# GadgetBox-Propeller.net
KiCad netlist of a schematic drawn in EAGLE
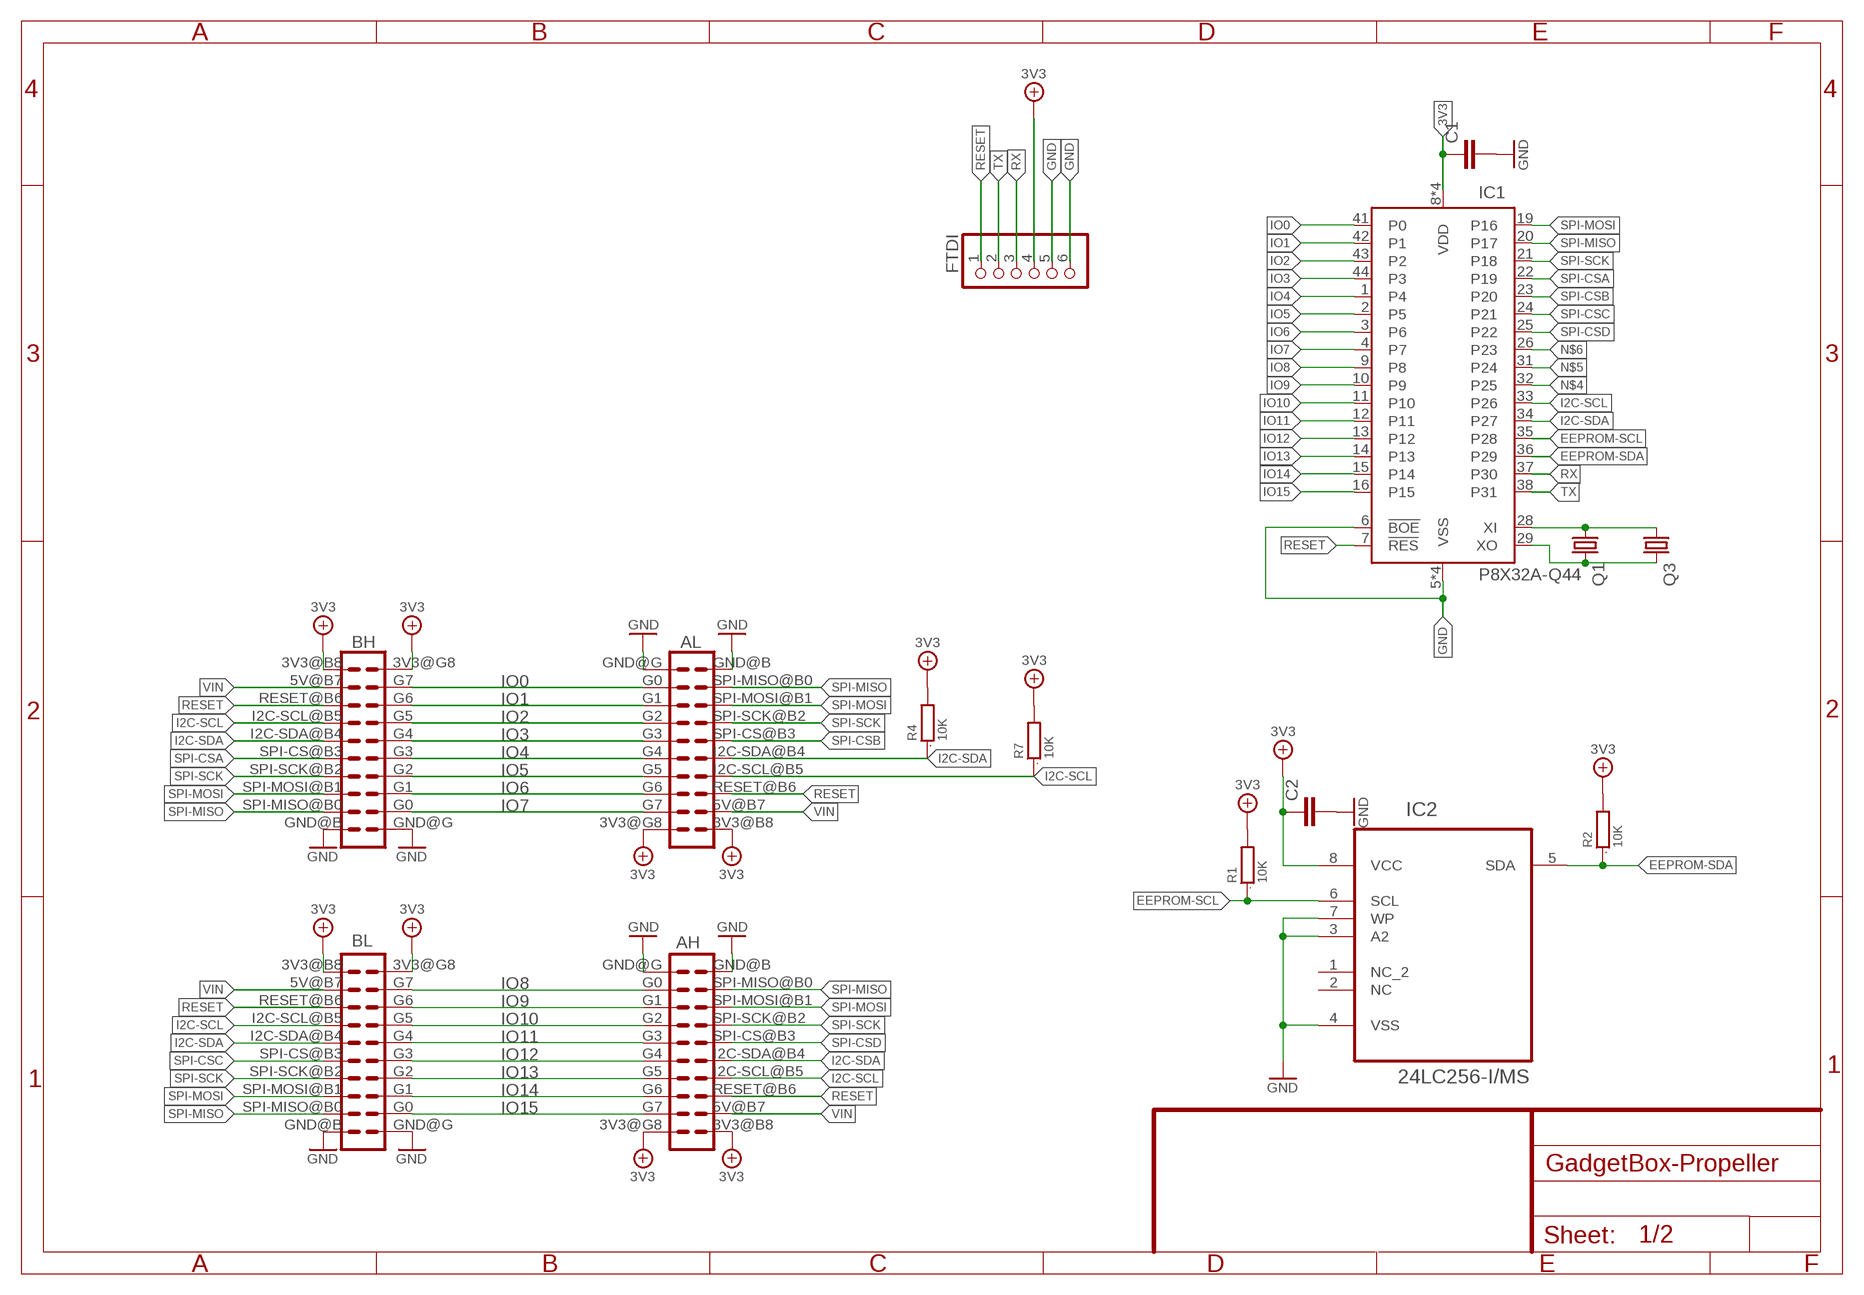
[diagram p0: schematic, sheet 1]
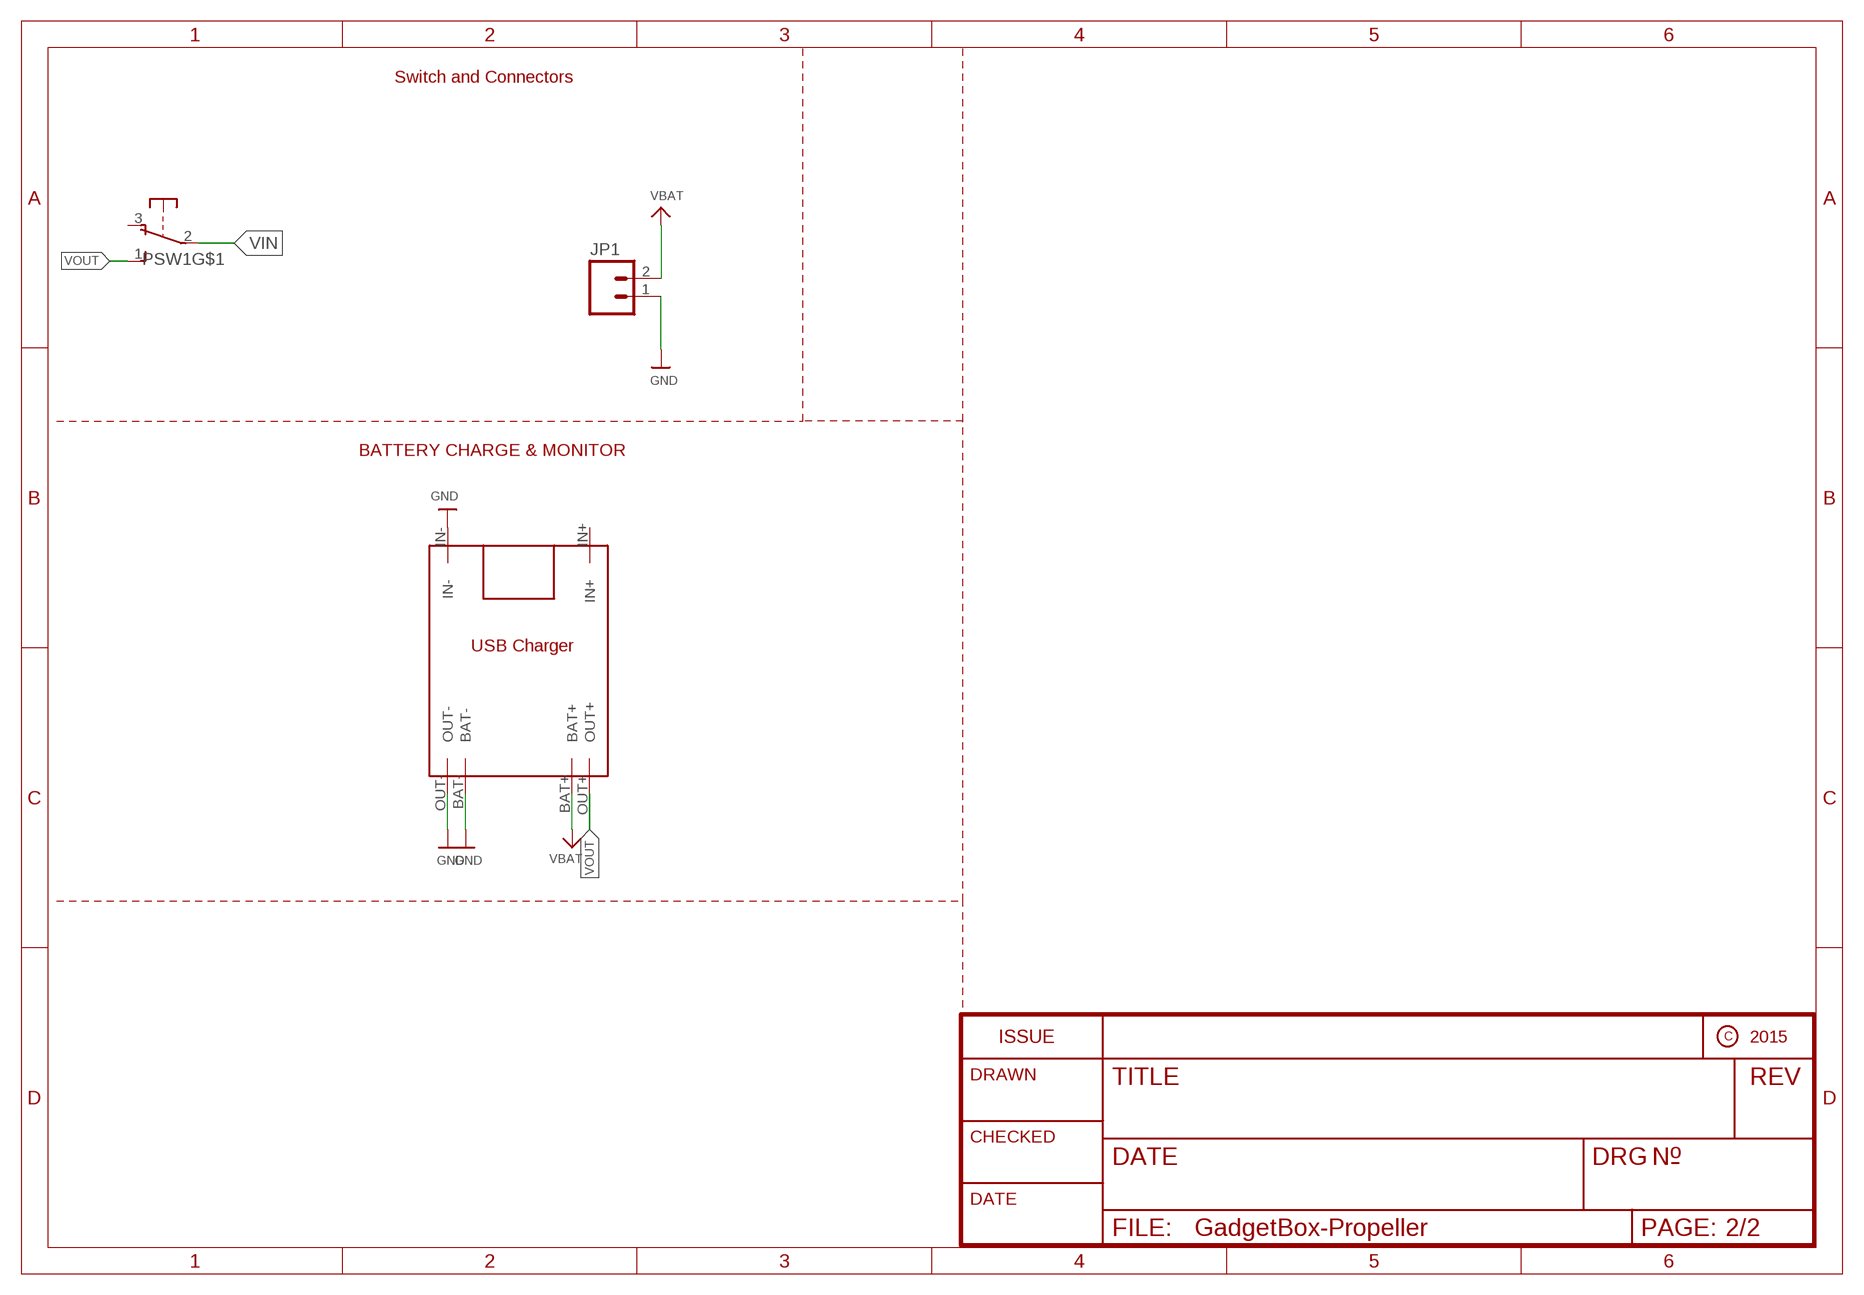
[diagram p1: schematic, sheet 2]

(export (version "E")
  (design (tool "Eeschema 10.0.6"))
  (components
    (comp (ref "JP1")
      (value "M02-JST-2-PTH-NO_SILK")
      (footprint "eagle-import:JST-2-PTH-NS")
      (libsource (lib "eagle-import") (part "M02-JST-2-PTH-NO_SILK"))
    )
    (comp (ref "PSW1")
      (value "OS102011MA1Q")
      (footprint "eagle-import:OS102011MA1Q")
      (fields
        (field (name "PARTNO") "OS102011MA1QN1,C&K Components,dk,CKN9559-ND,SWITCH SLIDE SPDT 100MA 12V , REF72")
      )
      (libsource (lib "eagle-import") (part "OS102011MA1Q"))
    )
    (comp (ref "U$5")
      (value "TP4056")
      (footprint "eagle-import:TP4056")
      (libsource (lib "eagle-import") (part "TP4056"))
    )
    (comp (ref "AH")
      (value "ECOGECOG_SLOT_ALT1")
      (footprint "eagle-import:ECOG_ALT1")
      (libsource (lib "eagle-import") (part "ECOGECOG_SLOT_ALT1"))
    )
    (comp (ref "AL")
      (value "ECOGECOG_SLOT_ALT1")
      (footprint "eagle-import:ECOG_ALT1")
      (libsource (lib "eagle-import") (part "ECOGECOG_SLOT_ALT1"))
    )
    (comp (ref "BH")
      (value "ECOGECOG_SLOT_ALT1")
      (footprint "eagle-import:ECOG_ALT1")
      (libsource (lib "eagle-import") (part "ECOGECOG_SLOT_ALT1"))
    )
    (comp (ref "BL")
      (value "ECOGECOG_SLOT_ALT1")
      (footprint "eagle-import:ECOG_ALT1")
      (libsource (lib "eagle-import") (part "ECOGECOG_SLOT_ALT1"))
    )
    (comp (ref "C1")
      (value "CAP0805")
      (footprint "eagle-import:0805")
      (libsource (lib "eagle-import") (part "CAP0805"))
    )
    (comp (ref "C2")
      (value "CAP0805")
      (footprint "eagle-import:0805")
      (libsource (lib "eagle-import") (part "CAP0805"))
    )
    (comp (ref "FTDI")
      (value "PINHD-1X6")
      (footprint "eagle-import:1X06")
      (libsource (lib "eagle-import") (part "PINHD-1X6"))
    )
    (comp (ref "IC1")
      (value "P8X32A-Q44")
      (footprint "eagle-import:LQFP44-10X10")
      (fields (field (name "MF") "Parallax Semiconductor"))
      (libsource (lib "eagle-import") (part "P8X32A-?Q44"))
    )
    (comp (ref "IC2")
      (value "24LC256-I/MS")
      (footprint "eagle-import:SOP65P490X110-8N")
      (libsource (lib "eagle-import") (part "24LC256-I/MS"))
    )
    (comp (ref "Q1")
      (value "CRYSTALSM49")
      (footprint "eagle-import:SM49")
      (libsource (lib "eagle-import") (part "CRYSTALSM49"))
    )
    (comp (ref "Q3")
      (value "CRYSTALHC49U-V")
      (footprint "eagle-import:HC49U-V")
      (libsource (lib "eagle-import") (part "CRYSTALHC49U-V"))
    )
    (comp (ref "R1")
      (value "10K")
      (footprint "eagle-import:0603")
      (fields
        (field (name "PARTNO") "RC0603JR-0710KL,YAGEO (VA),dk,311-10KGRCT-ND,RES SMD 10K OHM 5% 1/10W 0603 , REF36")
      )
      (libsource (lib "eagle-import") (part "R0603"))
    )
    (comp (ref "R2")
      (value "10K")
      (footprint "eagle-import:0603")
      (fields
        (field (name "PARTNO") "RC0603JR-0710KL,YAGEO (VA),dk,311-10KGRCT-ND,RES SMD 10K OHM 5% 1/10W 0603 , REF36")
      )
      (libsource (lib "eagle-import") (part "R0603"))
    )
    (comp (ref "R4")
      (value "10K")
      (footprint "eagle-import:0603")
      (fields
        (field (name "PARTNO") "RC0603JR-0710KL,YAGEO (VA),dk,311-10KGRCT-ND,RES SMD 10K OHM 5% 1/10W 0603 , REF36")
      )
      (libsource (lib "eagle-import") (part "R0603"))
    )
    (comp (ref "R7")
      (value "10K")
      (footprint "eagle-import:0603")
      (fields
        (field (name "PARTNO") "RC0603JR-0710KL,YAGEO (VA),dk,311-10KGRCT-ND,RES SMD 10K OHM 5% 1/10W 0603 , REF36")
      )
      (libsource (lib "eagle-import") (part "R0603"))
    )
  )
  (nets
    (net (code "1") (name "3V3") (class "Default")
      (node (ref "AH") (pin "3V3@B8") (pinfunction "3V3_3V3@B8") (pintype "passive"))
      (node (ref "AH") (pin "3V3@G8") (pinfunction "3V3_3V3@G8") (pintype "passive"))
      (node (ref "AL") (pin "3V3@B8") (pinfunction "3V3_3V3@B8") (pintype "passive"))
      (node (ref "AL") (pin "3V3@G8") (pinfunction "3V3_3V3@G8") (pintype "passive"))
      (node (ref "BH") (pin "3V3@B8") (pinfunction "3V3_3V3@B8") (pintype "passive"))
      (node (ref "BH") (pin "3V3@G8") (pinfunction "3V3_3V3@G8") (pintype "passive"))
      (node (ref "BL") (pin "3V3@B8") (pinfunction "3V3_3V3@B8") (pintype "passive"))
      (node (ref "BL") (pin "3V3@G8") (pinfunction "3V3_3V3@G8") (pintype "passive"))
      (node (ref "C1") (pin "1") (pinfunction "1_1") (pintype "passive"))
      (node (ref "C2") (pin "1") (pinfunction "1_1") (pintype "passive"))
      (node (ref "FTDI") (pin "4") (pinfunction "4_4") (pintype "passive"))
      (node (ref "IC1") (pin "18") (pinfunction "VDD_18") (pintype "power_in"))
      (node (ref "IC1") (pin "30") (pinfunction "VDD_30") (pintype "power_in"))
      (node (ref "IC1") (pin "40") (pinfunction "VDD_40") (pintype "power_in"))
      (node (ref "IC1") (pin "8") (pinfunction "VDD_8") (pintype "power_in"))
      (node (ref "IC2") (pin "8") (pinfunction "VCC_8") (pintype "power_in"))
      (node (ref "R1") (pin "2") (pinfunction "2_2") (pintype "passive"))
      (node (ref "R2") (pin "2") (pinfunction "2_2") (pintype "passive"))
      (node (ref "R4") (pin "2") (pinfunction "2_2") (pintype "passive"))
      (node (ref "R7") (pin "2") (pinfunction "2_2") (pintype "passive"))
    )
    (net (code "2") (name "EEPROM-SCL") (class "Default")
      (node (ref "IC1") (pin "35") (pinfunction "P28_35") (pintype "bidirectional"))
      (node (ref "IC2") (pin "6") (pinfunction "SCL_6") (pintype "input"))
      (node (ref "R1") (pin "1") (pinfunction "1_1") (pintype "passive"))
    )
    (net (code "3") (name "EEPROM-SDA") (class "Default")
      (node (ref "IC1") (pin "36") (pinfunction "P29_36") (pintype "bidirectional"))
      (node (ref "IC2") (pin "5") (pinfunction "SDA_5") (pintype "bidirectional"))
      (node (ref "R2") (pin "1") (pinfunction "1_1") (pintype "passive"))
    )
    (net (code "4") (name "GND") (class "Default")
      (node (ref "AH") (pin "GND@B") (pinfunction "GND_GND@B") (pintype "passive"))
      (node (ref "AH") (pin "GND@G") (pinfunction "GND_GND@G") (pintype "passive"))
      (node (ref "AL") (pin "GND@B") (pinfunction "GND_GND@B") (pintype "passive"))
      (node (ref "AL") (pin "GND@G") (pinfunction "GND_GND@G") (pintype "passive"))
      (node (ref "BH") (pin "GND@B") (pinfunction "GND_GND@B") (pintype "passive"))
      (node (ref "BH") (pin "GND@G") (pinfunction "GND_GND@G") (pintype "passive"))
      (node (ref "BL") (pin "GND@B") (pinfunction "GND_GND@B") (pintype "passive"))
      (node (ref "BL") (pin "GND@G") (pinfunction "GND_GND@G") (pintype "passive"))
      (node (ref "C1") (pin "2") (pinfunction "2_2") (pintype "passive"))
      (node (ref "C2") (pin "2") (pinfunction "2_2") (pintype "passive"))
      (node (ref "FTDI") (pin "5") (pinfunction "5_5") (pintype "passive"))
      (node (ref "FTDI") (pin "6") (pinfunction "6_6") (pintype "passive"))
      (node (ref "IC1") (pin "17") (pinfunction "VSS_17") (pintype "power_in"))
      (node (ref "IC1") (pin "27") (pinfunction "VSS_27") (pintype "power_in"))
      (node (ref "IC1") (pin "39") (pinfunction "VSS_39") (pintype "power_in"))
      (node (ref "IC1") (pin "5") (pinfunction "VSS_5") (pintype "power_in"))
      (node (ref "IC1") (pin "6") (pinfunction "~{BOE}_6") (pintype "input"))
      (node (ref "IC2") (pin "3") (pinfunction "A2_3") (pintype "input"))
      (node (ref "IC2") (pin "4") (pinfunction "VSS_4") (pintype "passive"))
      (node (ref "IC2") (pin "7") (pinfunction "WP_7") (pintype "input"))
      (node (ref "JP1") (pin "1") (pinfunction "1_1") (pintype "passive"))
      (node (ref "U$5") (pin "BAT-") (pinfunction "BAT-_BAT-") (pintype "bidirectional"))
      (node (ref "U$5") (pin "IN-") (pinfunction "IN-_IN-") (pintype "bidirectional"))
      (node (ref "U$5") (pin "OUT-") (pinfunction "OUT-_OUT-") (pintype "bidirectional"))
    )
    (net (code "5") (name "I2C-SCL") (class "Default")
      (node (ref "AH") (pin "I2C-SCL@B5") (pinfunction "I2C-SCL_I2C-SCL@B5") (pintype "passive"))
      (node (ref "AL") (pin "I2C-SCL@B5") (pinfunction "I2C-SCL_I2C-SCL@B5") (pintype "passive"))
      (node (ref "BH") (pin "I2C-SCL@B5") (pinfunction "I2C-SCL_I2C-SCL@B5") (pintype "passive"))
      (node (ref "BL") (pin "I2C-SCL@B5") (pinfunction "I2C-SCL_I2C-SCL@B5") (pintype "passive"))
      (node (ref "IC1") (pin "33") (pinfunction "P26_33") (pintype "bidirectional"))
      (node (ref "R7") (pin "1") (pinfunction "1_1") (pintype "passive"))
    )
    (net (code "6") (name "I2C-SDA") (class "Default")
      (node (ref "AH") (pin "I2C-SDA@B4") (pinfunction "I2C-SDA_I2C-SDA@B4") (pintype "passive"))
      (node (ref "AL") (pin "I2C-SDA@B4") (pinfunction "I2C-SDA_I2C-SDA@B4") (pintype "passive"))
      (node (ref "BH") (pin "I2C-SDA@B4") (pinfunction "I2C-SDA_I2C-SDA@B4") (pintype "passive"))
      (node (ref "BL") (pin "I2C-SDA@B4") (pinfunction "I2C-SDA_I2C-SDA@B4") (pintype "passive"))
      (node (ref "IC1") (pin "34") (pinfunction "P27_34") (pintype "bidirectional"))
      (node (ref "R4") (pin "1") (pinfunction "1_1") (pintype "passive"))
    )
    (net (code "7") (name "IO0") (class "Default")
      (node (ref "AL") (pin "G0") (pinfunction "G0_G0") (pintype "passive"))
      (node (ref "BH") (pin "G7") (pinfunction "G7_G7") (pintype "passive"))
      (node (ref "IC1") (pin "41") (pinfunction "P0_41") (pintype "bidirectional"))
    )
    (net (code "8") (name "IO1") (class "Default")
      (node (ref "AL") (pin "G1") (pinfunction "G1_G1") (pintype "passive"))
      (node (ref "BH") (pin "G6") (pinfunction "G6_G6") (pintype "passive"))
      (node (ref "IC1") (pin "42") (pinfunction "P1_42") (pintype "bidirectional"))
    )
    (net (code "9") (name "IO2") (class "Default")
      (node (ref "AL") (pin "G2") (pinfunction "G2_G2") (pintype "passive"))
      (node (ref "BH") (pin "G5") (pinfunction "G5_G5") (pintype "passive"))
      (node (ref "IC1") (pin "43") (pinfunction "P2_43") (pintype "bidirectional"))
    )
    (net (code "10") (name "IO3") (class "Default")
      (node (ref "AL") (pin "G3") (pinfunction "G3_G3") (pintype "passive"))
      (node (ref "BH") (pin "G4") (pinfunction "G4_G4") (pintype "passive"))
      (node (ref "IC1") (pin "44") (pinfunction "P3_44") (pintype "bidirectional"))
    )
    (net (code "11") (name "IO4") (class "Default")
      (node (ref "AL") (pin "G4") (pinfunction "G4_G4") (pintype "passive"))
      (node (ref "BH") (pin "G3") (pinfunction "G3_G3") (pintype "passive"))
      (node (ref "IC1") (pin "1") (pinfunction "P4_1") (pintype "bidirectional"))
    )
    (net (code "12") (name "IO5") (class "Default")
      (node (ref "AL") (pin "G5") (pinfunction "G5_G5") (pintype "passive"))
      (node (ref "BH") (pin "G2") (pinfunction "G2_G2") (pintype "passive"))
      (node (ref "IC1") (pin "2") (pinfunction "P5_2") (pintype "bidirectional"))
    )
    (net (code "13") (name "IO6") (class "Default")
      (node (ref "AL") (pin "G6") (pinfunction "G6_G6") (pintype "passive"))
      (node (ref "BH") (pin "G1") (pinfunction "G1_G1") (pintype "passive"))
      (node (ref "IC1") (pin "3") (pinfunction "P6_3") (pintype "bidirectional"))
    )
    (net (code "14") (name "IO7") (class "Default")
      (node (ref "AL") (pin "G7") (pinfunction "G7_G7") (pintype "passive"))
      (node (ref "BH") (pin "G0") (pinfunction "G0_G0") (pintype "passive"))
      (node (ref "IC1") (pin "4") (pinfunction "P7_4") (pintype "bidirectional"))
    )
    (net (code "15") (name "IO8") (class "Default")
      (node (ref "AH") (pin "G0") (pinfunction "G0_G0") (pintype "passive"))
      (node (ref "BL") (pin "G7") (pinfunction "G7_G7") (pintype "passive"))
      (node (ref "IC1") (pin "9") (pinfunction "P8_9") (pintype "bidirectional"))
    )
    (net (code "16") (name "IO9") (class "Default")
      (node (ref "AH") (pin "G1") (pinfunction "G1_G1") (pintype "passive"))
      (node (ref "BL") (pin "G6") (pinfunction "G6_G6") (pintype "passive"))
      (node (ref "IC1") (pin "10") (pinfunction "P9_10") (pintype "bidirectional"))
    )
    (net (code "17") (name "IO10") (class "Default")
      (node (ref "AH") (pin "G2") (pinfunction "G2_G2") (pintype "passive"))
      (node (ref "BL") (pin "G5") (pinfunction "G5_G5") (pintype "passive"))
      (node (ref "IC1") (pin "11") (pinfunction "P10_11") (pintype "bidirectional"))
    )
    (net (code "18") (name "IO11") (class "Default")
      (node (ref "AH") (pin "G3") (pinfunction "G3_G3") (pintype "passive"))
      (node (ref "BL") (pin "G4") (pinfunction "G4_G4") (pintype "passive"))
      (node (ref "IC1") (pin "12") (pinfunction "P11_12") (pintype "bidirectional"))
    )
    (net (code "19") (name "IO12") (class "Default")
      (node (ref "AH") (pin "G4") (pinfunction "G4_G4") (pintype "passive"))
      (node (ref "BL") (pin "G3") (pinfunction "G3_G3") (pintype "passive"))
      (node (ref "IC1") (pin "13") (pinfunction "P12_13") (pintype "bidirectional"))
    )
    (net (code "20") (name "IO13") (class "Default")
      (node (ref "AH") (pin "G5") (pinfunction "G5_G5") (pintype "passive"))
      (node (ref "BL") (pin "G2") (pinfunction "G2_G2") (pintype "passive"))
      (node (ref "IC1") (pin "14") (pinfunction "P13_14") (pintype "bidirectional"))
    )
    (net (code "21") (name "IO14") (class "Default")
      (node (ref "AH") (pin "G6") (pinfunction "G6_G6") (pintype "passive"))
      (node (ref "BL") (pin "G1") (pinfunction "G1_G1") (pintype "passive"))
      (node (ref "IC1") (pin "15") (pinfunction "P14_15") (pintype "bidirectional"))
    )
    (net (code "22") (name "IO15") (class "Default")
      (node (ref "AH") (pin "G7") (pinfunction "G7_G7") (pintype "passive"))
      (node (ref "BL") (pin "G0") (pinfunction "G0_G0") (pintype "passive"))
      (node (ref "IC1") (pin "16") (pinfunction "P15_16") (pintype "bidirectional"))
    )
    (net (code "23") (name "N$4") (class "Default")
      (node (ref "IC1") (pin "32") (pinfunction "P25_32") (pintype "bidirectional"))
    )
    (net (code "24") (name "N$5") (class "Default")
      (node (ref "IC1") (pin "31") (pinfunction "P24_31") (pintype "bidirectional"))
    )
    (net (code "25") (name "N$6") (class "Default")
      (node (ref "IC1") (pin "26") (pinfunction "P23_26") (pintype "bidirectional"))
    )
    (net (code "26") (name "Net-(IC1-XI)") (class "Default")
      (node (ref "IC1") (pin "28") (pinfunction "XI_28") (pintype "input"))
      (node (ref "Q1") (pin "1") (pinfunction "1_1") (pintype "passive"))
      (node (ref "Q3") (pin "1") (pinfunction "1_1") (pintype "passive"))
    )
    (net (code "27") (name "Net-(IC1-XO)") (class "Default")
      (node (ref "IC1") (pin "29") (pinfunction "XO_29") (pintype "output"))
      (node (ref "Q1") (pin "2") (pinfunction "2_2") (pintype "passive"))
      (node (ref "Q3") (pin "2") (pinfunction "2_2") (pintype "passive"))
    )
    (net (code "28") (name "RESET") (class "Default")
      (node (ref "AH") (pin "RESET@B6") (pinfunction "RESET_RESET@B6") (pintype "passive"))
      (node (ref "AL") (pin "RESET@B6") (pinfunction "RESET_RESET@B6") (pintype "passive"))
      (node (ref "BH") (pin "RESET@B6") (pinfunction "RESET_RESET@B6") (pintype "passive"))
      (node (ref "BL") (pin "RESET@B6") (pinfunction "RESET_RESET@B6") (pintype "passive"))
      (node (ref "FTDI") (pin "1") (pinfunction "1_1") (pintype "passive"))
      (node (ref "IC1") (pin "7") (pinfunction "~{RES}_7") (pintype "passive"))
    )
    (net (code "29") (name "RX") (class "Default")
      (node (ref "FTDI") (pin "3") (pinfunction "3_3") (pintype "passive"))
      (node (ref "IC1") (pin "37") (pinfunction "P30_37") (pintype "bidirectional"))
    )
    (net (code "30") (name "SPI-CSA") (class "Default")
      (node (ref "BH") (pin "SPI-CS@B3") (pinfunction "SPI-CS_SPI-CS@B3") (pintype "passive"))
      (node (ref "IC1") (pin "22") (pinfunction "P19_22") (pintype "bidirectional"))
    )
    (net (code "31") (name "SPI-CSB") (class "Default")
      (node (ref "AL") (pin "SPI-CS@B3") (pinfunction "SPI-CS_SPI-CS@B3") (pintype "passive"))
      (node (ref "IC1") (pin "23") (pinfunction "P20_23") (pintype "bidirectional"))
    )
    (net (code "32") (name "SPI-CSC") (class "Default")
      (node (ref "BL") (pin "SPI-CS@B3") (pinfunction "SPI-CS_SPI-CS@B3") (pintype "passive"))
      (node (ref "IC1") (pin "24") (pinfunction "P21_24") (pintype "bidirectional"))
    )
    (net (code "33") (name "SPI-CSD") (class "Default")
      (node (ref "AH") (pin "SPI-CS@B3") (pinfunction "SPI-CS_SPI-CS@B3") (pintype "passive"))
      (node (ref "IC1") (pin "25") (pinfunction "P22_25") (pintype "bidirectional"))
    )
    (net (code "34") (name "SPI-MISO") (class "Default")
      (node (ref "AH") (pin "SPI-MISO@B0") (pinfunction "SPI-MISO_SPI-MISO@B0") (pintype "passive"))
      (node (ref "AL") (pin "SPI-MISO@B0") (pinfunction "SPI-MISO_SPI-MISO@B0") (pintype "passive"))
      (node (ref "BH") (pin "SPI-MISO@B0") (pinfunction "SPI-MISO_SPI-MISO@B0") (pintype "passive"))
      (node (ref "BL") (pin "SPI-MISO@B0") (pinfunction "SPI-MISO_SPI-MISO@B0") (pintype "passive"))
      (node (ref "IC1") (pin "20") (pinfunction "P17_20") (pintype "bidirectional"))
    )
    (net (code "35") (name "SPI-MOSI") (class "Default")
      (node (ref "AH") (pin "SPI-MOSI@B1") (pinfunction "SPI-MOSI_SPI-MOSI@B1") (pintype "passive"))
      (node (ref "AL") (pin "SPI-MOSI@B1") (pinfunction "SPI-MOSI_SPI-MOSI@B1") (pintype "passive"))
      (node (ref "BH") (pin "SPI-MOSI@B1") (pinfunction "SPI-MOSI_SPI-MOSI@B1") (pintype "passive"))
      (node (ref "BL") (pin "SPI-MOSI@B1") (pinfunction "SPI-MOSI_SPI-MOSI@B1") (pintype "passive"))
      (node (ref "IC1") (pin "19") (pinfunction "P16_19") (pintype "bidirectional"))
    )
    (net (code "36") (name "SPI-SCK") (class "Default")
      (node (ref "AH") (pin "SPI-SCK@B2") (pinfunction "SPI-SCK_SPI-SCK@B2") (pintype "passive"))
      (node (ref "AL") (pin "SPI-SCK@B2") (pinfunction "SPI-SCK_SPI-SCK@B2") (pintype "passive"))
      (node (ref "BH") (pin "SPI-SCK@B2") (pinfunction "SPI-SCK_SPI-SCK@B2") (pintype "passive"))
      (node (ref "BL") (pin "SPI-SCK@B2") (pinfunction "SPI-SCK_SPI-SCK@B2") (pintype "passive"))
      (node (ref "IC1") (pin "21") (pinfunction "P18_21") (pintype "bidirectional"))
    )
    (net (code "37") (name "TX") (class "Default")
      (node (ref "FTDI") (pin "2") (pinfunction "2_2") (pintype "passive"))
      (node (ref "IC1") (pin "38") (pinfunction "P31_38") (pintype "bidirectional"))
    )
    (net (code "38") (name "VBAT") (class "Default")
      (node (ref "JP1") (pin "2") (pinfunction "2_2") (pintype "passive"))
      (node (ref "U$5") (pin "BAT+") (pinfunction "BAT+_BAT+") (pintype "bidirectional"))
    )
    (net (code "39") (name "VIN") (class "Default")
      (node (ref "AH") (pin "5V@B7") (pinfunction "5V_5V@B7") (pintype "passive"))
      (node (ref "AL") (pin "5V@B7") (pinfunction "5V_5V@B7") (pintype "passive"))
      (node (ref "BH") (pin "5V@B7") (pinfunction "5V_5V@B7") (pintype "passive"))
      (node (ref "BL") (pin "5V@B7") (pinfunction "5V_5V@B7") (pintype "passive"))
      (node (ref "PSW1") (pin "2") (pinfunction "P_2") (pintype "passive"))
    )
    (net (code "40") (name "VOUT") (class "Default")
      (node (ref "PSW1") (pin "1") (pinfunction "S_1") (pintype "passive"))
      (node (ref "U$5") (pin "OUT+") (pinfunction "OUT+_OUT+") (pintype "bidirectional"))
    )
    (net (code "41") (name "unconnected-(IC2-NC-Pad2)") (class "Default")
      (node (ref "IC2") (pin "2") (pinfunction "NC_2") (pintype "no_connect"))
    )
    (net (code "42") (name "unconnected-(IC2-NC_2-Pad1)") (class "Default")
      (node (ref "IC2") (pin "1") (pinfunction "NC_2_1") (pintype "no_connect"))
    )
    (net (code "43") (name "unconnected-(PSW1A-O-Pad3)") (class "Default")
      (node (ref "PSW1") (pin "3") (pinfunction "O_3") (pintype "passive"))
    )
    (net (code "44") (name "unconnected-(U$5-PadIN+)") (class "Default")
      (node (ref "U$5") (pin "IN+") (pinfunction "IN+_IN+") (pintype "bidirectional"))
    )
  )
)
